# Pasa_bajas.net
KiCad netlist of a schematic drawn in Altium Designer
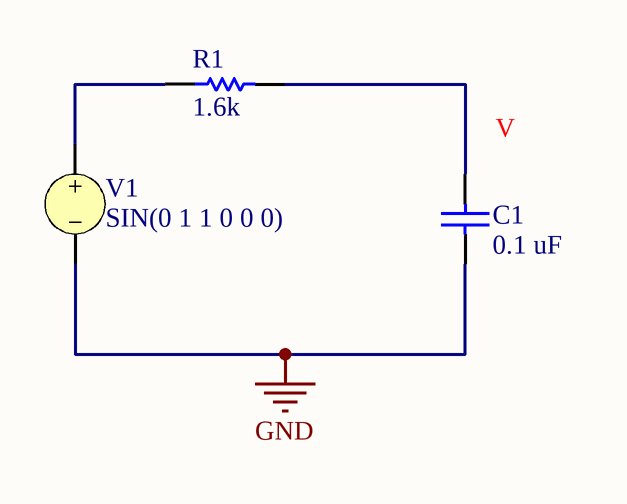
[diagram p0: Pasa_bajas.SchDoc]

(export (version "E")
  (design (tool "Eeschema 10.0.6"))
  (components
    (comp (ref "C1")
      (value "0.1 uF")
      (description "Capacitor")
      (libsource (lib "Simulation Generic Components") (part "Capacitor"))
    )
    (comp (ref "R1")
      (value "1.6k")
      (description "Resistor")
      (libsource (lib "Simulation Generic Components") (part "Resistor"))
    )
    (comp (ref "V1")
      (value "SIN(0 1 1 0 0 0)")
      (description "Voltage Source")
      (fields (field (name "PUBLISHER") "Altium Limited"))
      (libsource (lib "Simulation Generic Components") (part "VSRC"))
    )
  )
  (nets
    (net (code "1") (name "GND") (class "Default")
      (node (ref "C1") (pin "1") (pinfunction "1_1") (pintype "passive"))
      (node (ref "V1") (pin "2") (pinfunction "2_2") (pintype "passive"))
    )
    (net (code "2") (name "Net-(C1-Pad2)") (class "Default")
      (node (ref "C1") (pin "2") (pinfunction "2_2") (pintype "passive"))
      (node (ref "R1") (pin "2") (pinfunction "2_2") (pintype "passive"))
    )
    (net (code "3") (name "Net-(R1-Pad1)") (class "Default")
      (node (ref "R1") (pin "1") (pinfunction "1_1") (pintype "passive"))
      (node (ref "V1") (pin "1") (pinfunction "1_1") (pintype "passive"))
    )
  )
)
